# ST_link_V2.net
KiCad netlist of a schematic drawn in EAGLE
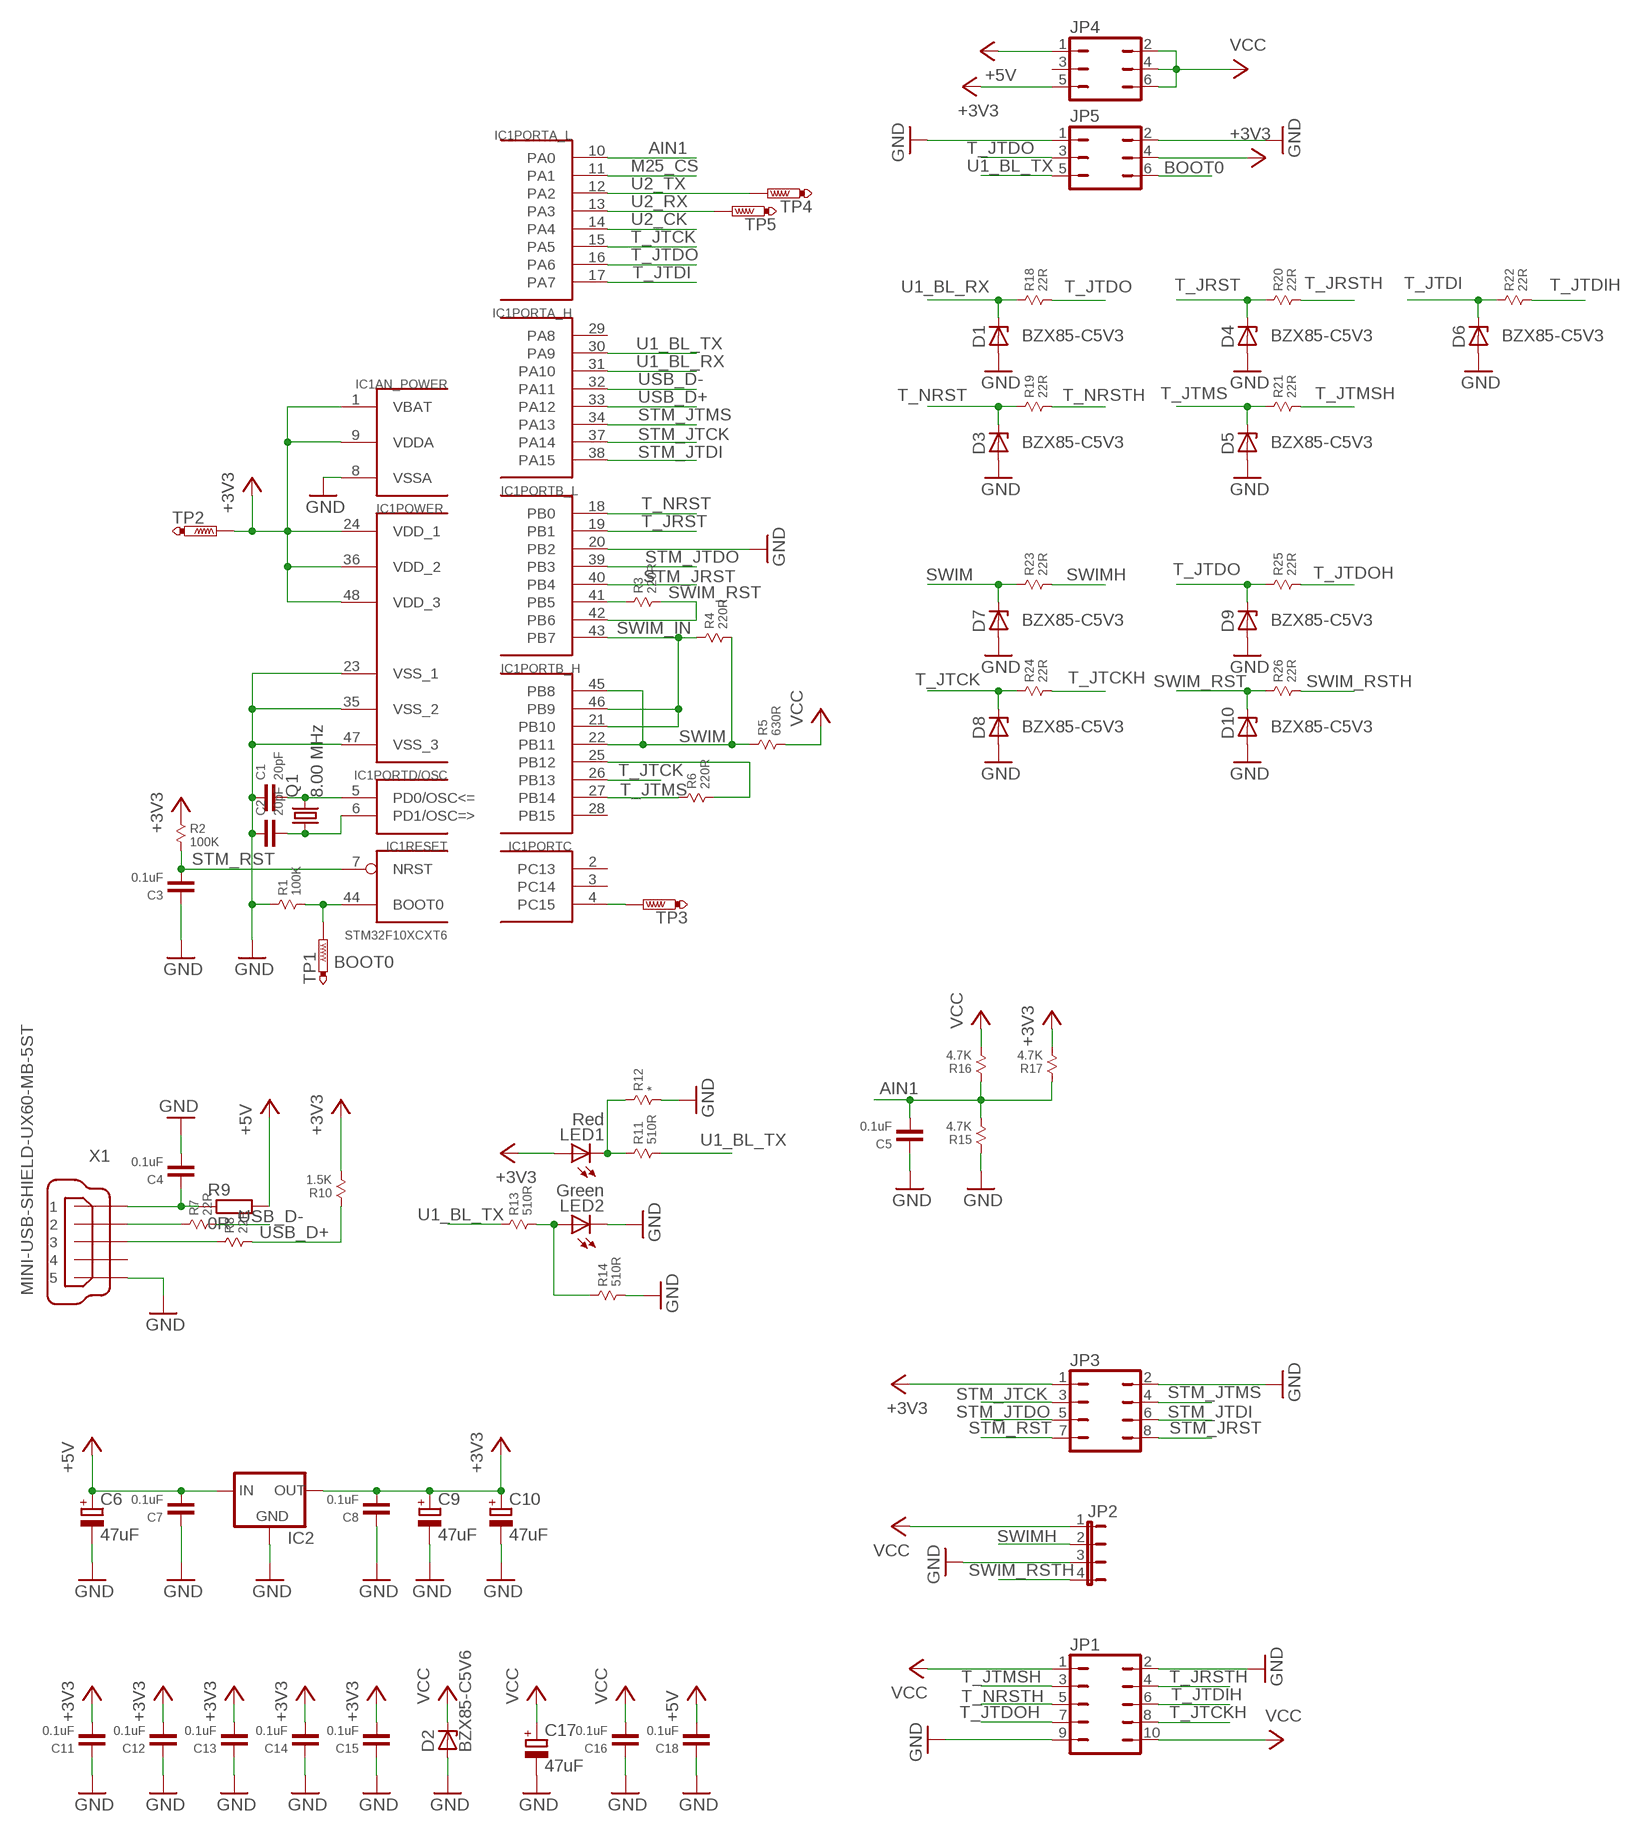
[diagram p0: schematic, sheet 1]

(export (version "E")
  (design (tool "Eeschema 10.0.6"))
  (components
    (comp (ref "C1")
      (value "20pF")
      (footprint "eagle-import:X893_0805")
      (libsource (lib "eagle-import") (part "X893_CAP-0805"))
    )
    (comp (ref "C2")
      (value "20pF")
      (footprint "eagle-import:X893_0805")
      (libsource (lib "eagle-import") (part "X893_CAP-0805"))
    )
    (comp (ref "C3")
      (value "0.1uF")
      (footprint "eagle-import:X893_0805")
      (libsource (lib "eagle-import") (part "X893_CAP-0805"))
    )
    (comp (ref "C4")
      (value "0.1uF")
      (footprint "eagle-import:X893_0805")
      (libsource (lib "eagle-import") (part "X893_CAP-0805"))
    )
    (comp (ref "C5")
      (value "0.1uF")
      (footprint "eagle-import:X893_0805")
      (libsource (lib "eagle-import") (part "X893_CAP-0805"))
    )
    (comp (ref "C6")
      (value "47uF")
      (footprint "eagle-import:SMC_B")
      (libsource (lib "eagle-import") (part "CPOL-EUSMCB"))
    )
    (comp (ref "C7")
      (value "0.1uF")
      (footprint "eagle-import:X893_0805")
      (libsource (lib "eagle-import") (part "X893_CAP-0805"))
    )
    (comp (ref "C8")
      (value "0.1uF")
      (footprint "eagle-import:X893_0805")
      (libsource (lib "eagle-import") (part "X893_CAP-0805"))
    )
    (comp (ref "C9")
      (value "47uF")
      (footprint "eagle-import:SMC_B")
      (libsource (lib "eagle-import") (part "CPOL-EUSMCB"))
    )
    (comp (ref "C10")
      (value "47uF")
      (footprint "eagle-import:SMC_B")
      (libsource (lib "eagle-import") (part "CPOL-EUSMCB"))
    )
    (comp (ref "C11")
      (value "0.1uF")
      (footprint "eagle-import:X893_0805")
      (libsource (lib "eagle-import") (part "X893_CAP-0805"))
    )
    (comp (ref "C12")
      (value "0.1uF")
      (footprint "eagle-import:X893_0805")
      (libsource (lib "eagle-import") (part "X893_CAP-0805"))
    )
    (comp (ref "C13")
      (value "0.1uF")
      (footprint "eagle-import:X893_0805")
      (libsource (lib "eagle-import") (part "X893_CAP-0805"))
    )
    (comp (ref "C14")
      (value "0.1uF")
      (footprint "eagle-import:X893_0805")
      (libsource (lib "eagle-import") (part "X893_CAP-0805"))
    )
    (comp (ref "C15")
      (value "0.1uF")
      (footprint "eagle-import:X893_0805")
      (libsource (lib "eagle-import") (part "X893_CAP-0805"))
    )
    (comp (ref "C16")
      (value "0.1uF")
      (footprint "eagle-import:X893_0805")
      (libsource (lib "eagle-import") (part "X893_CAP-0805"))
    )
    (comp (ref "C17")
      (value "47uF")
      (footprint "eagle-import:SMC_B")
      (libsource (lib "eagle-import") (part "CPOL-EUSMCB"))
    )
    (comp (ref "C18")
      (value "0.1uF")
      (footprint "eagle-import:X893_0805")
      (libsource (lib "eagle-import") (part "X893_CAP-0805"))
    )
    (comp (ref "D1")
      (value "BZX85-C5V3")
      (footprint "eagle-import:SOD80C")
      (libsource (lib "eagle-import") (part "ZENER-DIODESOD80C"))
    )
    (comp (ref "D2")
      (value "BZX85-C5V6")
      (footprint "eagle-import:SOD80C")
      (libsource (lib "eagle-import") (part "ZENER-DIODESOD80C"))
    )
    (comp (ref "D3")
      (value "BZX85-C5V3")
      (footprint "eagle-import:SOD80C")
      (libsource (lib "eagle-import") (part "ZENER-DIODESOD80C"))
    )
    (comp (ref "D4")
      (value "BZX85-C5V3")
      (footprint "eagle-import:SOD80C")
      (libsource (lib "eagle-import") (part "ZENER-DIODESOD80C"))
    )
    (comp (ref "D5")
      (value "BZX85-C5V3")
      (footprint "eagle-import:SOD80C")
      (libsource (lib "eagle-import") (part "ZENER-DIODESOD80C"))
    )
    (comp (ref "D6")
      (value "BZX85-C5V3")
      (footprint "eagle-import:SOD80C")
      (libsource (lib "eagle-import") (part "ZENER-DIODESOD80C"))
    )
    (comp (ref "D7")
      (value "BZX85-C5V3")
      (footprint "eagle-import:SOD80C")
      (libsource (lib "eagle-import") (part "ZENER-DIODESOD80C"))
    )
    (comp (ref "D8")
      (value "BZX85-C5V3")
      (footprint "eagle-import:SOD80C")
      (libsource (lib "eagle-import") (part "ZENER-DIODESOD80C"))
    )
    (comp (ref "D9")
      (value "BZX85-C5V3")
      (footprint "eagle-import:SOD80C")
      (libsource (lib "eagle-import") (part "ZENER-DIODESOD80C"))
    )
    (comp (ref "D10")
      (value "BZX85-C5V3")
      (footprint "eagle-import:SOD80C")
      (libsource (lib "eagle-import") (part "ZENER-DIODESOD80C"))
    )
    (comp (ref "IC1")
      (value "STM32F10XCXT6")
      (footprint "eagle-import:TQFP48")
      (libsource (lib "eagle-import") (part "STM32F10XCXT6"))
    )
    (comp (ref "IC2")
      (value "LM1117")
      (footprint "eagle-import:SOT223")
      (libsource (lib "eagle-import") (part "LM1117"))
    )
    (comp (ref "JP1")
      (value "JP5Q")
      (footprint "eagle-import:JP5Q")
      (libsource (lib "eagle-import") (part "JP5Q"))
    )
    (comp (ref "JP2")
      (value "JP4E")
      (footprint "eagle-import:JP4")
      (libsource (lib "eagle-import") (part "JP4E"))
    )
    (comp (ref "JP3")
      (value "JP4Q")
      (footprint "eagle-import:JP4Q")
      (libsource (lib "eagle-import") (part "JP4Q"))
    )
    (comp (ref "JP4")
      (value "JP3Q")
      (footprint "eagle-import:JP3Q")
      (libsource (lib "eagle-import") (part "JP3Q"))
    )
    (comp (ref "JP5")
      (value "JP3Q")
      (footprint "eagle-import:JP3Q")
      (libsource (lib "eagle-import") (part "JP3Q"))
    )
    (comp (ref "LED1")
      (value "Red")
      (footprint "eagle-import:SML0805")
      (libsource (lib "eagle-import") (part "LEDSML0805"))
    )
    (comp (ref "LED2")
      (value "Green")
      (footprint "eagle-import:SML0805")
      (libsource (lib "eagle-import") (part "LEDSML0805"))
    )
    (comp (ref "Q1")
      (value "8.00 MHz")
      (footprint "eagle-import:HC49U70")
      (libsource (lib "eagle-import") (part "CRYSTALHC49U70"))
    )
    (comp (ref "R1")
      (value "100K")
      (footprint "eagle-import:X893_0805")
      (libsource (lib "eagle-import") (part "X893_RESISTOR-0805"))
    )
    (comp (ref "R2")
      (value "100K")
      (footprint "eagle-import:X893_0805")
      (libsource (lib "eagle-import") (part "X893_RESISTOR-0805"))
    )
    (comp (ref "R3")
      (value "220R")
      (footprint "eagle-import:X893_0805")
      (libsource (lib "eagle-import") (part "X893_RESISTOR-0805"))
    )
    (comp (ref "R4")
      (value "220R")
      (footprint "eagle-import:X893_0805")
      (libsource (lib "eagle-import") (part "X893_RESISTOR-0805"))
    )
    (comp (ref "R5")
      (value "630R")
      (footprint "eagle-import:X893_0805")
      (libsource (lib "eagle-import") (part "X893_RESISTOR-0805"))
    )
    (comp (ref "R6")
      (value "220R")
      (footprint "eagle-import:X893_0805")
      (libsource (lib "eagle-import") (part "X893_RESISTOR-0805"))
    )
    (comp (ref "R7")
      (value "22R")
      (footprint "eagle-import:X893_0805")
      (libsource (lib "eagle-import") (part "X893_RESISTOR-0805"))
    )
    (comp (ref "R8")
      (value "22R")
      (footprint "eagle-import:X893_0805")
      (libsource (lib "eagle-import") (part "X893_RESISTOR-0805"))
    )
    (comp (ref "R9")
      (value "0R")
      (footprint "eagle-import:R1206")
      (libsource (lib "eagle-import") (part "R-EU_R1206"))
    )
    (comp (ref "R10")
      (value "1.5K")
      (footprint "eagle-import:X893_0805")
      (libsource (lib "eagle-import") (part "X893_RESISTOR-0805"))
    )
    (comp (ref "R11")
      (value "510R")
      (footprint "eagle-import:X893_0805")
      (libsource (lib "eagle-import") (part "X893_RESISTOR-0805"))
    )
    (comp (ref "R12")
      (value "*")
      (footprint "eagle-import:X893_0805")
      (libsource (lib "eagle-import") (part "X893_RESISTOR-0805"))
    )
    (comp (ref "R13")
      (value "510R")
      (footprint "eagle-import:X893_0805")
      (libsource (lib "eagle-import") (part "X893_RESISTOR-0805"))
    )
    (comp (ref "R14")
      (value "510R")
      (footprint "eagle-import:X893_0805")
      (libsource (lib "eagle-import") (part "X893_RESISTOR-0805"))
    )
    (comp (ref "R15")
      (value "4.7K")
      (footprint "eagle-import:X893_0805")
      (libsource (lib "eagle-import") (part "X893_RESISTOR-0805"))
    )
    (comp (ref "R16")
      (value "4.7K")
      (footprint "eagle-import:X893_0805")
      (libsource (lib "eagle-import") (part "X893_RESISTOR-0805"))
    )
    (comp (ref "R17")
      (value "4.7K")
      (footprint "eagle-import:X893_0805")
      (libsource (lib "eagle-import") (part "X893_RESISTOR-0805"))
    )
    (comp (ref "R18")
      (value "22R")
      (footprint "eagle-import:X893_0805")
      (libsource (lib "eagle-import") (part "X893_RESISTOR-0805"))
    )
    (comp (ref "R19")
      (value "22R")
      (footprint "eagle-import:X893_0805")
      (libsource (lib "eagle-import") (part "X893_RESISTOR-0805"))
    )
    (comp (ref "R20")
      (value "22R")
      (footprint "eagle-import:X893_0805")
      (libsource (lib "eagle-import") (part "X893_RESISTOR-0805"))
    )
    (comp (ref "R21")
      (value "22R")
      (footprint "eagle-import:X893_0805")
      (libsource (lib "eagle-import") (part "X893_RESISTOR-0805"))
    )
    (comp (ref "R22")
      (value "22R")
      (footprint "eagle-import:X893_0805")
      (libsource (lib "eagle-import") (part "X893_RESISTOR-0805"))
    )
    (comp (ref "R23")
      (value "22R")
      (footprint "eagle-import:X893_0805")
      (libsource (lib "eagle-import") (part "X893_RESISTOR-0805"))
    )
    (comp (ref "R24")
      (value "22R")
      (footprint "eagle-import:X893_0805")
      (libsource (lib "eagle-import") (part "X893_RESISTOR-0805"))
    )
    (comp (ref "R25")
      (value "22R")
      (footprint "eagle-import:X893_0805")
      (libsource (lib "eagle-import") (part "X893_RESISTOR-0805"))
    )
    (comp (ref "R26")
      (value "22R")
      (footprint "eagle-import:X893_0805")
      (libsource (lib "eagle-import") (part "X893_RESISTOR-0805"))
    )
    (comp (ref "TP1")
      (value "PTR1TP19R")
      (footprint "eagle-import:TP19R")
      (libsource (lib "eagle-import") (part "PTR1TP19R"))
    )
    (comp (ref "TP2")
      (value "PTR1TP19R")
      (footprint "eagle-import:TP19R")
      (libsource (lib "eagle-import") (part "PTR1TP19R"))
    )
    (comp (ref "TP3")
      (value "PTR1TP19R")
      (footprint "eagle-import:TP19R")
      (libsource (lib "eagle-import") (part "PTR1TP19R"))
    )
    (comp (ref "TP4")
      (value "PTR1TP19R")
      (footprint "eagle-import:TP19R")
      (libsource (lib "eagle-import") (part "PTR1TP19R"))
    )
    (comp (ref "TP5")
      (value "PTR1TP19R")
      (footprint "eagle-import:TP19R")
      (libsource (lib "eagle-import") (part "PTR1TP19R"))
    )
    (comp (ref "X1")
      (value "MINI-USB-SHIELD-UX60-MB-5ST")
      (footprint "eagle-import:UX60-MB-5ST")
      (libsource (lib "eagle-import") (part "MINI-USB-SHIELD-UX60-MB-5ST"))
    )
  )
  (nets
    (net (code "1") (name "+3V3") (class "Default")
      (node (ref "C10") (pin "+") (pinfunction "+_+") (pintype "passive"))
      (node (ref "C11") (pin "1") (pinfunction "1_1") (pintype "passive"))
      (node (ref "C12") (pin "1") (pinfunction "1_1") (pintype "passive"))
      (node (ref "C13") (pin "1") (pinfunction "1_1") (pintype "passive"))
      (node (ref "C14") (pin "1") (pinfunction "1_1") (pintype "passive"))
      (node (ref "C15") (pin "1") (pinfunction "1_1") (pintype "passive"))
      (node (ref "C8") (pin "1") (pinfunction "1_1") (pintype "passive"))
      (node (ref "C9") (pin "+") (pinfunction "+_+") (pintype "passive"))
      (node (ref "IC1") (pin "1") (pinfunction "VBAT_1") (pintype "power_in"))
      (node (ref "IC1") (pin "24") (pinfunction "VDD_1_24") (pintype "power_in"))
      (node (ref "IC1") (pin "36") (pinfunction "VDD_2_36") (pintype "power_in"))
      (node (ref "IC1") (pin "48") (pinfunction "VDD_3_48") (pintype "power_in"))
      (node (ref "IC1") (pin "9") (pinfunction "VDDA_9") (pintype "power_in"))
      (node (ref "IC2") (pin "2") (pinfunction "OUT_2") (pintype "passive"))
      (node (ref "JP3") (pin "1") (pinfunction "1_1") (pintype "passive"))
      (node (ref "JP4") (pin "5") (pinfunction "5_5") (pintype "passive"))
      (node (ref "JP5") (pin "4") (pinfunction "4_4") (pintype "passive"))
      (node (ref "LED1") (pin "A") (pinfunction "A_A") (pintype "passive"))
      (node (ref "R10") (pin "2") (pinfunction "2_2") (pintype "passive"))
      (node (ref "R17") (pin "2") (pinfunction "2_2") (pintype "passive"))
      (node (ref "R2") (pin "1") (pinfunction "1_1") (pintype "passive"))
      (node (ref "TP2") (pin "TP") (pinfunction "TP_TP") (pintype "input"))
    )
    (net (code "2") (name "+5V") (class "Default")
      (node (ref "C18") (pin "1") (pinfunction "1_1") (pintype "passive"))
      (node (ref "C6") (pin "+") (pinfunction "+_+") (pintype "passive"))
      (node (ref "C7") (pin "1") (pinfunction "1_1") (pintype "passive"))
      (node (ref "IC2") (pin "3") (pinfunction "IN_3") (pintype "input"))
      (node (ref "JP4") (pin "1") (pinfunction "1_1") (pintype "passive"))
      (node (ref "R9") (pin "2") (pinfunction "2_2") (pintype "passive"))
    )
    (net (code "3") (name "/AIN1") (class "Default")
      (node (ref "C5") (pin "1") (pinfunction "1_1") (pintype "passive"))
      (node (ref "IC1") (pin "10") (pinfunction "PA0_10") (pintype "bidirectional"))
      (node (ref "R15") (pin "2") (pinfunction "2_2") (pintype "passive"))
      (node (ref "R16") (pin "1") (pinfunction "1_1") (pintype "passive"))
      (node (ref "R17") (pin "1") (pinfunction "1_1") (pintype "passive"))
    )
    (net (code "4") (name "/BOOT0") (class "Default")
      (node (ref "IC1") (pin "44") (pinfunction "BOOT0_44") (pintype "input"))
      (node (ref "JP5") (pin "6") (pinfunction "6_6") (pintype "passive"))
      (node (ref "R1") (pin "2") (pinfunction "2_2") (pintype "passive"))
      (node (ref "TP1") (pin "TP") (pinfunction "TP_TP") (pintype "input"))
    )
    (net (code "5") (name "/M25_CS") (class "Default")
      (node (ref "IC1") (pin "11") (pinfunction "PA1_11") (pintype "bidirectional"))
    )
    (net (code "6") (name "/STM_JRST") (class "Default")
      (node (ref "IC1") (pin "40") (pinfunction "PB4_40") (pintype "bidirectional"))
      (node (ref "JP3") (pin "8") (pinfunction "8_8") (pintype "passive"))
    )
    (net (code "7") (name "/STM_JTCK") (class "Default")
      (node (ref "IC1") (pin "37") (pinfunction "PA14_37") (pintype "bidirectional"))
      (node (ref "JP3") (pin "3") (pinfunction "3_3") (pintype "passive"))
    )
    (net (code "8") (name "/STM_JTDI") (class "Default")
      (node (ref "IC1") (pin "38") (pinfunction "PA15_38") (pintype "bidirectional"))
      (node (ref "JP3") (pin "6") (pinfunction "6_6") (pintype "passive"))
    )
    (net (code "9") (name "/STM_JTDO") (class "Default")
      (node (ref "IC1") (pin "39") (pinfunction "PB3_39") (pintype "bidirectional"))
      (node (ref "JP3") (pin "5") (pinfunction "5_5") (pintype "passive"))
    )
    (net (code "10") (name "/STM_JTMS") (class "Default")
      (node (ref "IC1") (pin "34") (pinfunction "PA13_34") (pintype "bidirectional"))
      (node (ref "JP3") (pin "4") (pinfunction "4_4") (pintype "passive"))
    )
    (net (code "11") (name "/STM_RST") (class "Default")
      (node (ref "C3") (pin "1") (pinfunction "1_1") (pintype "passive"))
      (node (ref "IC1") (pin "7") (pinfunction "NRST_7") (pintype "input"))
      (node (ref "JP3") (pin "7") (pinfunction "7_7") (pintype "passive"))
      (node (ref "R2") (pin "2") (pinfunction "2_2") (pintype "passive"))
    )
    (net (code "12") (name "/SWIM") (class "Default")
      (node (ref "D7") (pin "C") (pinfunction "C_C") (pintype "passive"))
      (node (ref "IC1") (pin "22") (pinfunction "PB11_22") (pintype "bidirectional"))
      (node (ref "IC1") (pin "45") (pinfunction "PB8_45") (pintype "bidirectional"))
      (node (ref "R23") (pin "1") (pinfunction "1_1") (pintype "passive"))
      (node (ref "R4") (pin "2") (pinfunction "2_2") (pintype "passive"))
      (node (ref "R5") (pin "1") (pinfunction "1_1") (pintype "passive"))
    )
    (net (code "13") (name "/SWIMH") (class "Default")
      (node (ref "JP2") (pin "2") (pinfunction "2_2") (pintype "passive"))
      (node (ref "R23") (pin "2") (pinfunction "2_2") (pintype "passive"))
    )
    (net (code "14") (name "/SWIM_IN") (class "Default")
      (node (ref "IC1") (pin "21") (pinfunction "PB10_21") (pintype "bidirectional"))
      (node (ref "IC1") (pin "43") (pinfunction "PB7_43") (pintype "bidirectional"))
      (node (ref "IC1") (pin "46") (pinfunction "PB9_46") (pintype "bidirectional"))
      (node (ref "R4") (pin "1") (pinfunction "1_1") (pintype "passive"))
    )
    (net (code "15") (name "/SWIM_RST") (class "Default")
      (node (ref "D10") (pin "C") (pinfunction "C_C") (pintype "passive"))
      (node (ref "IC1") (pin "42") (pinfunction "PB6_42") (pintype "bidirectional"))
      (node (ref "R26") (pin "1") (pinfunction "1_1") (pintype "passive"))
      (node (ref "R3") (pin "2") (pinfunction "2_2") (pintype "passive"))
    )
    (net (code "16") (name "/SWIM_RSTH") (class "Default")
      (node (ref "JP2") (pin "4") (pinfunction "4_4") (pintype "passive"))
      (node (ref "R26") (pin "2") (pinfunction "2_2") (pintype "passive"))
    )
    (net (code "17") (name "/T_JRST") (class "Default")
      (node (ref "D4") (pin "C") (pinfunction "C_C") (pintype "passive"))
      (node (ref "IC1") (pin "19") (pinfunction "PB1_19") (pintype "bidirectional"))
      (node (ref "R20") (pin "1") (pinfunction "1_1") (pintype "passive"))
    )
    (net (code "18") (name "/T_JRSTH") (class "Default")
      (node (ref "JP1") (pin "4") (pinfunction "4_4") (pintype "passive"))
      (node (ref "R20") (pin "2") (pinfunction "2_2") (pintype "passive"))
    )
    (net (code "19") (name "/T_JTCK") (class "Default")
      (node (ref "D8") (pin "C") (pinfunction "C_C") (pintype "passive"))
      (node (ref "IC1") (pin "15") (pinfunction "PA5_15") (pintype "bidirectional"))
      (node (ref "IC1") (pin "26") (pinfunction "PB13_26") (pintype "bidirectional"))
      (node (ref "R24") (pin "1") (pinfunction "1_1") (pintype "passive"))
    )
    (net (code "20") (name "/T_JTCKH") (class "Default")
      (node (ref "JP1") (pin "8") (pinfunction "8_8") (pintype "passive"))
      (node (ref "R24") (pin "2") (pinfunction "2_2") (pintype "passive"))
    )
    (net (code "21") (name "/T_JTDI") (class "Default")
      (node (ref "D6") (pin "C") (pinfunction "C_C") (pintype "passive"))
      (node (ref "IC1") (pin "17") (pinfunction "PA7_17") (pintype "bidirectional"))
      (node (ref "R22") (pin "1") (pinfunction "1_1") (pintype "passive"))
    )
    (net (code "22") (name "/T_JTDIH") (class "Default")
      (node (ref "JP1") (pin "6") (pinfunction "6_6") (pintype "passive"))
      (node (ref "R22") (pin "2") (pinfunction "2_2") (pintype "passive"))
    )
    (net (code "23") (name "/T_JTDO") (class "Default")
      (node (ref "D9") (pin "C") (pinfunction "C_C") (pintype "passive"))
      (node (ref "IC1") (pin "16") (pinfunction "PA6_16") (pintype "bidirectional"))
      (node (ref "JP5") (pin "3") (pinfunction "3_3") (pintype "passive"))
      (node (ref "R18") (pin "2") (pinfunction "2_2") (pintype "passive"))
      (node (ref "R25") (pin "1") (pinfunction "1_1") (pintype "passive"))
    )
    (net (code "24") (name "/T_JTDOH") (class "Default")
      (node (ref "JP1") (pin "7") (pinfunction "7_7") (pintype "passive"))
      (node (ref "R25") (pin "2") (pinfunction "2_2") (pintype "passive"))
    )
    (net (code "25") (name "/T_JTMS") (class "Default")
      (node (ref "D5") (pin "C") (pinfunction "C_C") (pintype "passive"))
      (node (ref "IC1") (pin "27") (pinfunction "PB14_27") (pintype "bidirectional"))
      (node (ref "R21") (pin "1") (pinfunction "1_1") (pintype "passive"))
      (node (ref "R6") (pin "1") (pinfunction "1_1") (pintype "passive"))
    )
    (net (code "26") (name "/T_JTMSH") (class "Default")
      (node (ref "JP1") (pin "3") (pinfunction "3_3") (pintype "passive"))
      (node (ref "R21") (pin "2") (pinfunction "2_2") (pintype "passive"))
    )
    (net (code "27") (name "/T_NRST") (class "Default")
      (node (ref "D3") (pin "C") (pinfunction "C_C") (pintype "passive"))
      (node (ref "IC1") (pin "18") (pinfunction "PB0_18") (pintype "bidirectional"))
      (node (ref "R19") (pin "1") (pinfunction "1_1") (pintype "passive"))
    )
    (net (code "28") (name "/T_NRSTH") (class "Default")
      (node (ref "JP1") (pin "5") (pinfunction "5_5") (pintype "passive"))
      (node (ref "R19") (pin "2") (pinfunction "2_2") (pintype "passive"))
    )
    (net (code "29") (name "/U1_BL_RX") (class "Default")
      (node (ref "D1") (pin "C") (pinfunction "C_C") (pintype "passive"))
      (node (ref "IC1") (pin "31") (pinfunction "PA10_31") (pintype "bidirectional"))
      (node (ref "R18") (pin "1") (pinfunction "1_1") (pintype "passive"))
    )
    (net (code "30") (name "/U1_BL_TX") (class "Default")
      (node (ref "IC1") (pin "30") (pinfunction "PA9_30") (pintype "bidirectional"))
      (node (ref "JP5") (pin "5") (pinfunction "5_5") (pintype "passive"))
      (node (ref "R11") (pin "2") (pinfunction "2_2") (pintype "passive"))
      (node (ref "R13") (pin "1") (pinfunction "1_1") (pintype "passive"))
    )
    (net (code "31") (name "/U2_CK") (class "Default")
      (node (ref "IC1") (pin "14") (pinfunction "PA4_14") (pintype "bidirectional"))
    )
    (net (code "32") (name "/U2_RX") (class "Default")
      (node (ref "IC1") (pin "13") (pinfunction "PA3_13") (pintype "bidirectional"))
      (node (ref "TP5") (pin "TP") (pinfunction "TP_TP") (pintype "input"))
    )
    (net (code "33") (name "/U2_TX") (class "Default")
      (node (ref "IC1") (pin "12") (pinfunction "PA2_12") (pintype "bidirectional"))
      (node (ref "TP4") (pin "TP") (pinfunction "TP_TP") (pintype "input"))
    )
    (net (code "34") (name "/USB_D+") (class "Default")
      (node (ref "IC1") (pin "33") (pinfunction "PA12_33") (pintype "bidirectional"))
      (node (ref "R10") (pin "1") (pinfunction "1_1") (pintype "passive"))
      (node (ref "R8") (pin "2") (pinfunction "2_2") (pintype "passive"))
    )
    (net (code "35") (name "/USB_D-") (class "Default")
      (node (ref "IC1") (pin "32") (pinfunction "PA11_32") (pintype "bidirectional"))
      (node (ref "R7") (pin "2") (pinfunction "2_2") (pintype "passive"))
    )
    (net (code "36") (name "GND") (class "Default")
      (node (ref "C1") (pin "2") (pinfunction "2_2") (pintype "passive"))
      (node (ref "C10") (pin "-") (pinfunction "-_-") (pintype "passive"))
      (node (ref "C11") (pin "2") (pinfunction "2_2") (pintype "passive"))
      (node (ref "C12") (pin "2") (pinfunction "2_2") (pintype "passive"))
      (node (ref "C13") (pin "2") (pinfunction "2_2") (pintype "passive"))
      (node (ref "C14") (pin "2") (pinfunction "2_2") (pintype "passive"))
      (node (ref "C15") (pin "2") (pinfunction "2_2") (pintype "passive"))
      (node (ref "C16") (pin "2") (pinfunction "2_2") (pintype "passive"))
      (node (ref "C17") (pin "-") (pinfunction "-_-") (pintype "passive"))
      (node (ref "C18") (pin "2") (pinfunction "2_2") (pintype "passive"))
      (node (ref "C2") (pin "2") (pinfunction "2_2") (pintype "passive"))
      (node (ref "C3") (pin "2") (pinfunction "2_2") (pintype "passive"))
      (node (ref "C4") (pin "1") (pinfunction "1_1") (pintype "passive"))
      (node (ref "C5") (pin "2") (pinfunction "2_2") (pintype "passive"))
      (node (ref "C6") (pin "-") (pinfunction "-_-") (pintype "passive"))
      (node (ref "C7") (pin "2") (pinfunction "2_2") (pintype "passive"))
      (node (ref "C8") (pin "2") (pinfunction "2_2") (pintype "passive"))
      (node (ref "C9") (pin "-") (pinfunction "-_-") (pintype "passive"))
      (node (ref "D1") (pin "A") (pinfunction "A_A") (pintype "passive"))
      (node (ref "D10") (pin "A") (pinfunction "A_A") (pintype "passive"))
      (node (ref "D2") (pin "A") (pinfunction "A_A") (pintype "passive"))
      (node (ref "D3") (pin "A") (pinfunction "A_A") (pintype "passive"))
      (node (ref "D4") (pin "A") (pinfunction "A_A") (pintype "passive"))
      (node (ref "D5") (pin "A") (pinfunction "A_A") (pintype "passive"))
      (node (ref "D6") (pin "A") (pinfunction "A_A") (pintype "passive"))
      (node (ref "D7") (pin "A") (pinfunction "A_A") (pintype "passive"))
      (node (ref "D8") (pin "A") (pinfunction "A_A") (pintype "passive"))
      (node (ref "D9") (pin "A") (pinfunction "A_A") (pintype "passive"))
      (node (ref "IC1") (pin "20") (pinfunction "PB2_20") (pintype "bidirectional"))
      (node (ref "IC1") (pin "23") (pinfunction "VSS_1_23") (pintype "power_in"))
      (node (ref "IC1") (pin "35") (pinfunction "VSS_2_35") (pintype "power_in"))
      (node (ref "IC1") (pin "47") (pinfunction "VSS_3_47") (pintype "power_in"))
      (node (ref "IC1") (pin "8") (pinfunction "VSSA_8") (pintype "power_in"))
      (node (ref "IC2") (pin "1") (pinfunction "GND_1") (pintype "input"))
      (node (ref "JP1") (pin "2") (pinfunction "2_2") (pintype "passive"))
      (node (ref "JP1") (pin "9") (pinfunction "9_9") (pintype "passive"))
      (node (ref "JP2") (pin "3") (pinfunction "3_3") (pintype "passive"))
      (node (ref "JP3") (pin "2") (pinfunction "2_2") (pintype "passive"))
      (node (ref "JP5") (pin "1") (pinfunction "1_1") (pintype "passive"))
      (node (ref "JP5") (pin "2") (pinfunction "2_2") (pintype "passive"))
      (node (ref "LED2") (pin "C") (pinfunction "C_C") (pintype "passive"))
      (node (ref "R1") (pin "1") (pinfunction "1_1") (pintype "passive"))
      (node (ref "R12") (pin "2") (pinfunction "2_2") (pintype "passive"))
      (node (ref "R14") (pin "2") (pinfunction "2_2") (pintype "passive"))
      (node (ref "R15") (pin "1") (pinfunction "1_1") (pintype "passive"))
      (node (ref "X1") (pin "5") (pinfunction "5_5") (pintype "input"))
    )
    (net (code "37") (name "Net-(C4-Pad2)") (class "Default")
      (node (ref "C4") (pin "2") (pinfunction "2_2") (pintype "passive"))
      (node (ref "R9") (pin "1") (pinfunction "1_1") (pintype "passive"))
      (node (ref "X1") (pin "1") (pinfunction "1_1") (pintype "input"))
    )
    (net (code "38") (name "Net-(IC1D-PB12)") (class "Default")
      (node (ref "IC1") (pin "25") (pinfunction "PB12_25") (pintype "bidirectional"))
      (node (ref "R6") (pin "2") (pinfunction "2_2") (pintype "passive"))
    )
    (net (code "39") (name "Net-(IC1E-PB5)") (class "Default")
      (node (ref "IC1") (pin "41") (pinfunction "PB5_41") (pintype "bidirectional"))
      (node (ref "R3") (pin "1") (pinfunction "1_1") (pintype "passive"))
    )
    (net (code "40") (name "Net-(IC1F-PC15)") (class "Default")
      (node (ref "IC1") (pin "4") (pinfunction "PC15_4") (pintype "bidirectional"))
      (node (ref "TP3") (pin "TP") (pinfunction "TP_TP") (pintype "input"))
    )
    (net (code "41") (name "Net-(IC1G-PD0{slash}OSC<=)") (class "Default")
      (node (ref "C1") (pin "1") (pinfunction "1_1") (pintype "passive"))
      (node (ref "IC1") (pin "5") (pinfunction "PD0/OSC<=_5") (pintype "bidirectional"))
      (node (ref "Q1") (pin "2") (pinfunction "2_2") (pintype "passive"))
    )
    (net (code "42") (name "Net-(IC1G-PD1{slash}OSC=>)") (class "Default")
      (node (ref "C2") (pin "1") (pinfunction "1_1") (pintype "passive"))
      (node (ref "IC1") (pin "6") (pinfunction "PD1/OSC=>_6") (pintype "bidirectional"))
      (node (ref "Q1") (pin "1") (pinfunction "1_1") (pintype "passive"))
    )
    (net (code "43") (name "Net-(LED1-PadC)") (class "Default")
      (node (ref "LED1") (pin "C") (pinfunction "C_C") (pintype "passive"))
      (node (ref "R11") (pin "1") (pinfunction "1_1") (pintype "passive"))
      (node (ref "R12") (pin "1") (pinfunction "1_1") (pintype "passive"))
    )
    (net (code "44") (name "Net-(LED2-PadA)") (class "Default")
      (node (ref "LED2") (pin "A") (pinfunction "A_A") (pintype "passive"))
      (node (ref "R13") (pin "2") (pinfunction "2_2") (pintype "passive"))
      (node (ref "R14") (pin "1") (pinfunction "1_1") (pintype "passive"))
    )
    (net (code "45") (name "Net-(R7-Pad1)") (class "Default")
      (node (ref "R7") (pin "1") (pinfunction "1_1") (pintype "passive"))
      (node (ref "X1") (pin "2") (pinfunction "2_2") (pintype "input"))
    )
    (net (code "46") (name "Net-(R8-Pad1)") (class "Default")
      (node (ref "R8") (pin "1") (pinfunction "1_1") (pintype "passive"))
      (node (ref "X1") (pin "3") (pinfunction "3_3") (pintype "input"))
    )
    (net (code "47") (name "VCC") (class "Default")
      (node (ref "C16") (pin "1") (pinfunction "1_1") (pintype "passive"))
      (node (ref "C17") (pin "+") (pinfunction "+_+") (pintype "passive"))
      (node (ref "D2") (pin "C") (pinfunction "C_C") (pintype "passive"))
      (node (ref "JP1") (pin "1") (pinfunction "1_1") (pintype "passive"))
      (node (ref "JP1") (pin "10") (pinfunction "10_10") (pintype "passive"))
      (node (ref "JP2") (pin "1") (pinfunction "1_1") (pintype "passive"))
      (node (ref "JP4") (pin "2") (pinfunction "2_2") (pintype "passive"))
      (node (ref "JP4") (pin "4") (pinfunction "4_4") (pintype "passive"))
      (node (ref "JP4") (pin "6") (pinfunction "6_6") (pintype "passive"))
      (node (ref "R16") (pin "2") (pinfunction "2_2") (pintype "passive"))
      (node (ref "R5") (pin "2") (pinfunction "2_2") (pintype "passive"))
    )
    (net (code "48") (name "unconnected-(IC1B-PA8-Pad29)") (class "Default")
      (node (ref "IC1") (pin "29") (pinfunction "PA8_29") (pintype "bidirectional"))
    )
    (net (code "49") (name "unconnected-(IC1D-PB15-Pad28)") (class "Default")
      (node (ref "IC1") (pin "28") (pinfunction "PB15_28") (pintype "bidirectional"))
    )
    (net (code "50") (name "unconnected-(IC1F-PC13-Pad2)") (class "Default")
      (node (ref "IC1") (pin "2") (pinfunction "PC13_2") (pintype "bidirectional"))
    )
    (net (code "51") (name "unconnected-(IC1F-PC14-Pad3)") (class "Default")
      (node (ref "IC1") (pin "3") (pinfunction "PC14_3") (pintype "bidirectional"))
    )
    (net (code "52") (name "unconnected-(JP4-Pad3)") (class "Default")
      (node (ref "JP4") (pin "3") (pinfunction "3_3") (pintype "passive"))
    )
    (net (code "53") (name "unconnected-(X1-Pad4)") (class "Default")
      (node (ref "X1") (pin "4") (pinfunction "4_4") (pintype "input"))
    )
  )
)
